# TEST1.net
KiCad netlist of a schematic drawn in EAGLE
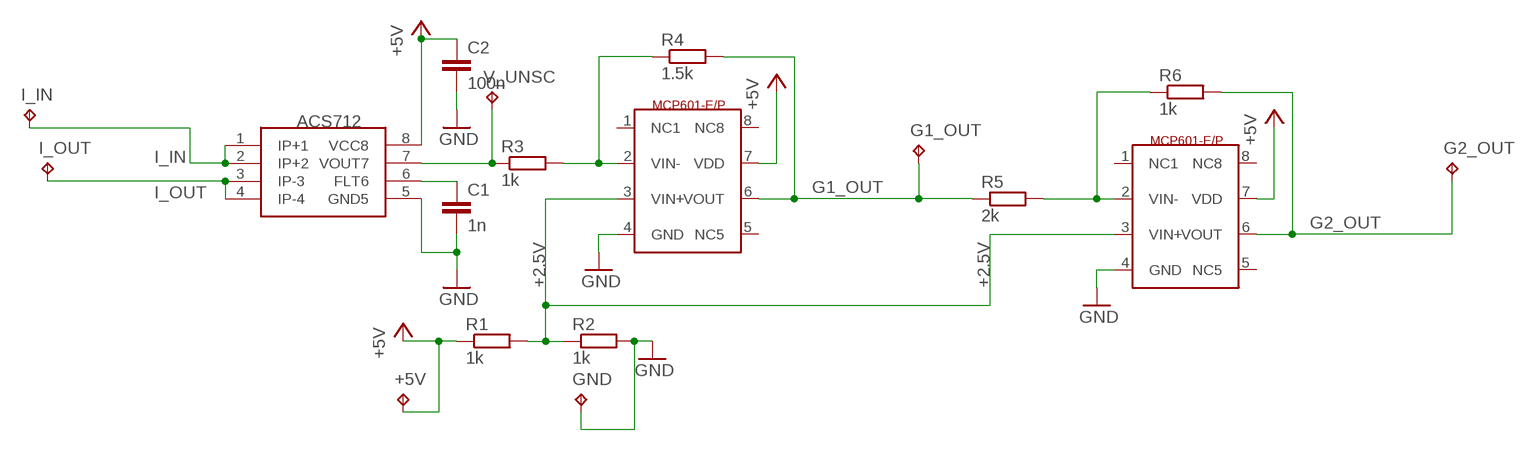
[diagram p0: schematic, sheet 1]

(export (version "E")
  (design (tool "Eeschema 10.0.6"))
  (components
    (comp (ref "+5V")
      (value "TPPAD1-17Y")
      (footprint "eagle-import:P1-17Y")
      (libsource (lib "eagle-import") (part "TPPAD1-17Y"))
    )
    (comp (ref "C1")
      (value "1n")
      (footprint "eagle-import:C050-050X075")
      (libsource (lib "eagle-import") (part "C-EU050-050X075"))
    )
    (comp (ref "C2")
      (value "100n")
      (footprint "eagle-import:C050-050X075")
      (libsource (lib "eagle-import") (part "C-EU050-050X075"))
    )
    (comp (ref "G1_OUT")
      (value "TPPAD1-17Y")
      (footprint "eagle-import:P1-17Y")
      (libsource (lib "eagle-import") (part "TPPAD1-17Y"))
    )
    (comp (ref "G2_OUT")
      (value "TPPAD1-17Y")
      (footprint "eagle-import:P1-17Y")
      (libsource (lib "eagle-import") (part "TPPAD1-17Y"))
    )
    (comp (ref "GND")
      (value "TPPAD1-17Y")
      (footprint "eagle-import:P1-17Y")
      (libsource (lib "eagle-import") (part "TPPAD1-17Y"))
    )
    (comp (ref "I_IN")
      (value "TPPAD1-17Y")
      (footprint "eagle-import:P1-17Y")
      (libsource (lib "eagle-import") (part "TPPAD1-17Y"))
    )
    (comp (ref "I_OUT")
      (value "TPPAD1-17Y")
      (footprint "eagle-import:P1-17Y")
      (libsource (lib "eagle-import") (part "TPPAD1-17Y"))
    )
    (comp (ref "R1")
      (value "1k")
      (footprint "eagle-import:0309_12")
      (libsource (lib "eagle-import") (part "R-EU_0309/12"))
    )
    (comp (ref "R2")
      (value "1k")
      (footprint "eagle-import:0309_12")
      (libsource (lib "eagle-import") (part "R-EU_0309/12"))
    )
    (comp (ref "R3")
      (value "1k")
      (footprint "eagle-import:0309_12")
      (libsource (lib "eagle-import") (part "R-EU_0309/12"))
    )
    (comp (ref "R4")
      (value "1.5k")
      (footprint "eagle-import:0309_12")
      (libsource (lib "eagle-import") (part "R-EU_0309/12"))
    )
    (comp (ref "R5")
      (value "2k")
      (footprint "eagle-import:0309_12")
      (libsource (lib "eagle-import") (part "R-EU_0309/12"))
    )
    (comp (ref "R6")
      (value "1k")
      (footprint "eagle-import:0309_12")
      (libsource (lib "eagle-import") (part "R-EU_0309/12"))
    )
    (comp (ref "U$1")
      (value "ACS712")
      (footprint "eagle-import:SOIC8")
      (libsource (lib "eagle-import") (part "ACS712"))
    )
    (comp (ref "U$2")
      (value "MCP601")
      (footprint "eagle-import:PDIP8")
      (libsource (lib "eagle-import") (part "MCP601"))
    )
    (comp (ref "U$3")
      (value "MCP601")
      (footprint "eagle-import:PDIP8")
      (libsource (lib "eagle-import") (part "MCP601"))
    )
    (comp (ref "V_UNSC")
      (value "TPPAD1-17Y")
      (footprint "eagle-import:P1-17Y")
      (libsource (lib "eagle-import") (part "TPPAD1-17Y"))
    )
  )
  (nets
    (net (code "1") (name "+5V") (class "Default")
      (node (ref "+5V") (pin "TP") (pinfunction "TP_TP") (pintype "input"))
      (node (ref "C2") (pin "1") (pinfunction "1_1") (pintype "passive"))
      (node (ref "R1") (pin "1") (pinfunction "1_1") (pintype "passive"))
      (node (ref "U$1") (pin "8") (pinfunction "VCC8_8") (pintype "power_in"))
      (node (ref "U$2") (pin "7") (pinfunction "VDD_7") (pintype "power_in"))
      (node (ref "U$3") (pin "7") (pinfunction "VDD_7") (pintype "power_in"))
    )
    (net (code "2") (name "/+2.5V") (class "Default")
      (node (ref "R1") (pin "2") (pinfunction "2_2") (pintype "passive"))
      (node (ref "R2") (pin "1") (pinfunction "1_1") (pintype "passive"))
      (node (ref "U$2") (pin "3") (pinfunction "VIN+_3") (pintype "bidirectional"))
      (node (ref "U$3") (pin "3") (pinfunction "VIN+_3") (pintype "bidirectional"))
    )
    (net (code "3") (name "/G1_OUT") (class "Default")
      (node (ref "G1_OUT") (pin "TP") (pinfunction "TP_TP") (pintype "input"))
      (node (ref "R4") (pin "2") (pinfunction "2_2") (pintype "passive"))
      (node (ref "R5") (pin "1") (pinfunction "1_1") (pintype "passive"))
      (node (ref "U$2") (pin "6") (pinfunction "VOUT_6") (pintype "bidirectional"))
    )
    (net (code "4") (name "/G2_OUT") (class "Default")
      (node (ref "G2_OUT") (pin "TP") (pinfunction "TP_TP") (pintype "input"))
      (node (ref "R6") (pin "2") (pinfunction "2_2") (pintype "passive"))
      (node (ref "U$3") (pin "6") (pinfunction "VOUT_6") (pintype "bidirectional"))
    )
    (net (code "5") (name "/I_IN") (class "Default")
      (node (ref "I_IN") (pin "TP") (pinfunction "TP_TP") (pintype "input"))
      (node (ref "U$1") (pin "1") (pinfunction "IP+1_1") (pintype "bidirectional"))
      (node (ref "U$1") (pin "2") (pinfunction "IP+2_2") (pintype "bidirectional"))
    )
    (net (code "6") (name "/I_OUT") (class "Default")
      (node (ref "I_OUT") (pin "TP") (pinfunction "TP_TP") (pintype "input"))
      (node (ref "U$1") (pin "3") (pinfunction "IP-3_3") (pintype "bidirectional"))
      (node (ref "U$1") (pin "4") (pinfunction "IP-4_4") (pintype "bidirectional"))
    )
    (net (code "7") (name "GND") (class "Default")
      (node (ref "C1") (pin "2") (pinfunction "2_2") (pintype "passive"))
      (node (ref "C2") (pin "2") (pinfunction "2_2") (pintype "passive"))
      (node (ref "GND") (pin "TP") (pinfunction "TP_TP") (pintype "input"))
      (node (ref "R2") (pin "2") (pinfunction "2_2") (pintype "passive"))
      (node (ref "U$1") (pin "5") (pinfunction "GND5_5") (pintype "power_in"))
      (node (ref "U$2") (pin "4") (pinfunction "GND_4") (pintype "power_in"))
      (node (ref "U$3") (pin "4") (pinfunction "GND_4") (pintype "power_in"))
    )
    (net (code "8") (name "Net-(U$1-FLT6)") (class "Default")
      (node (ref "C1") (pin "1") (pinfunction "1_1") (pintype "passive"))
      (node (ref "U$1") (pin "6") (pinfunction "FLT6_6") (pintype "passive"))
    )
    (net (code "9") (name "Net-(U$1-VOUT7)") (class "Default")
      (node (ref "R3") (pin "1") (pinfunction "1_1") (pintype "passive"))
      (node (ref "U$1") (pin "7") (pinfunction "VOUT7_7") (pintype "output"))
      (node (ref "V_UNSC") (pin "TP") (pinfunction "TP_TP") (pintype "input"))
    )
    (net (code "10") (name "Net-(U$2-VIN-)") (class "Default")
      (node (ref "R3") (pin "2") (pinfunction "2_2") (pintype "passive"))
      (node (ref "R4") (pin "1") (pinfunction "1_1") (pintype "passive"))
      (node (ref "U$2") (pin "2") (pinfunction "VIN-_2") (pintype "bidirectional"))
    )
    (net (code "11") (name "Net-(U$3-VIN-)") (class "Default")
      (node (ref "R5") (pin "2") (pinfunction "2_2") (pintype "passive"))
      (node (ref "R6") (pin "1") (pinfunction "1_1") (pintype "passive"))
      (node (ref "U$3") (pin "2") (pinfunction "VIN-_2") (pintype "bidirectional"))
    )
    (net (code "12") (name "unconnected-(U$2-NC1-Pad1)") (class "Default")
      (node (ref "U$2") (pin "1") (pinfunction "NC1_1") (pintype "no_connect"))
    )
    (net (code "13") (name "unconnected-(U$2-NC5-Pad5)") (class "Default")
      (node (ref "U$2") (pin "5") (pinfunction "NC5_5") (pintype "no_connect"))
    )
    (net (code "14") (name "unconnected-(U$2-NC8-Pad8)") (class "Default")
      (node (ref "U$2") (pin "8") (pinfunction "NC8_8") (pintype "no_connect"))
    )
    (net (code "15") (name "unconnected-(U$3-NC1-Pad1)") (class "Default")
      (node (ref "U$3") (pin "1") (pinfunction "NC1_1") (pintype "no_connect"))
    )
    (net (code "16") (name "unconnected-(U$3-NC5-Pad5)") (class "Default")
      (node (ref "U$3") (pin "5") (pinfunction "NC5_5") (pintype "no_connect"))
    )
    (net (code "17") (name "unconnected-(U$3-NC8-Pad8)") (class "Default")
      (node (ref "U$3") (pin "8") (pinfunction "NC8_8") (pintype "no_connect"))
    )
  )
)
